# EEM_Connectors.net
KiCad netlist of a schematic drawn in Altium Designer
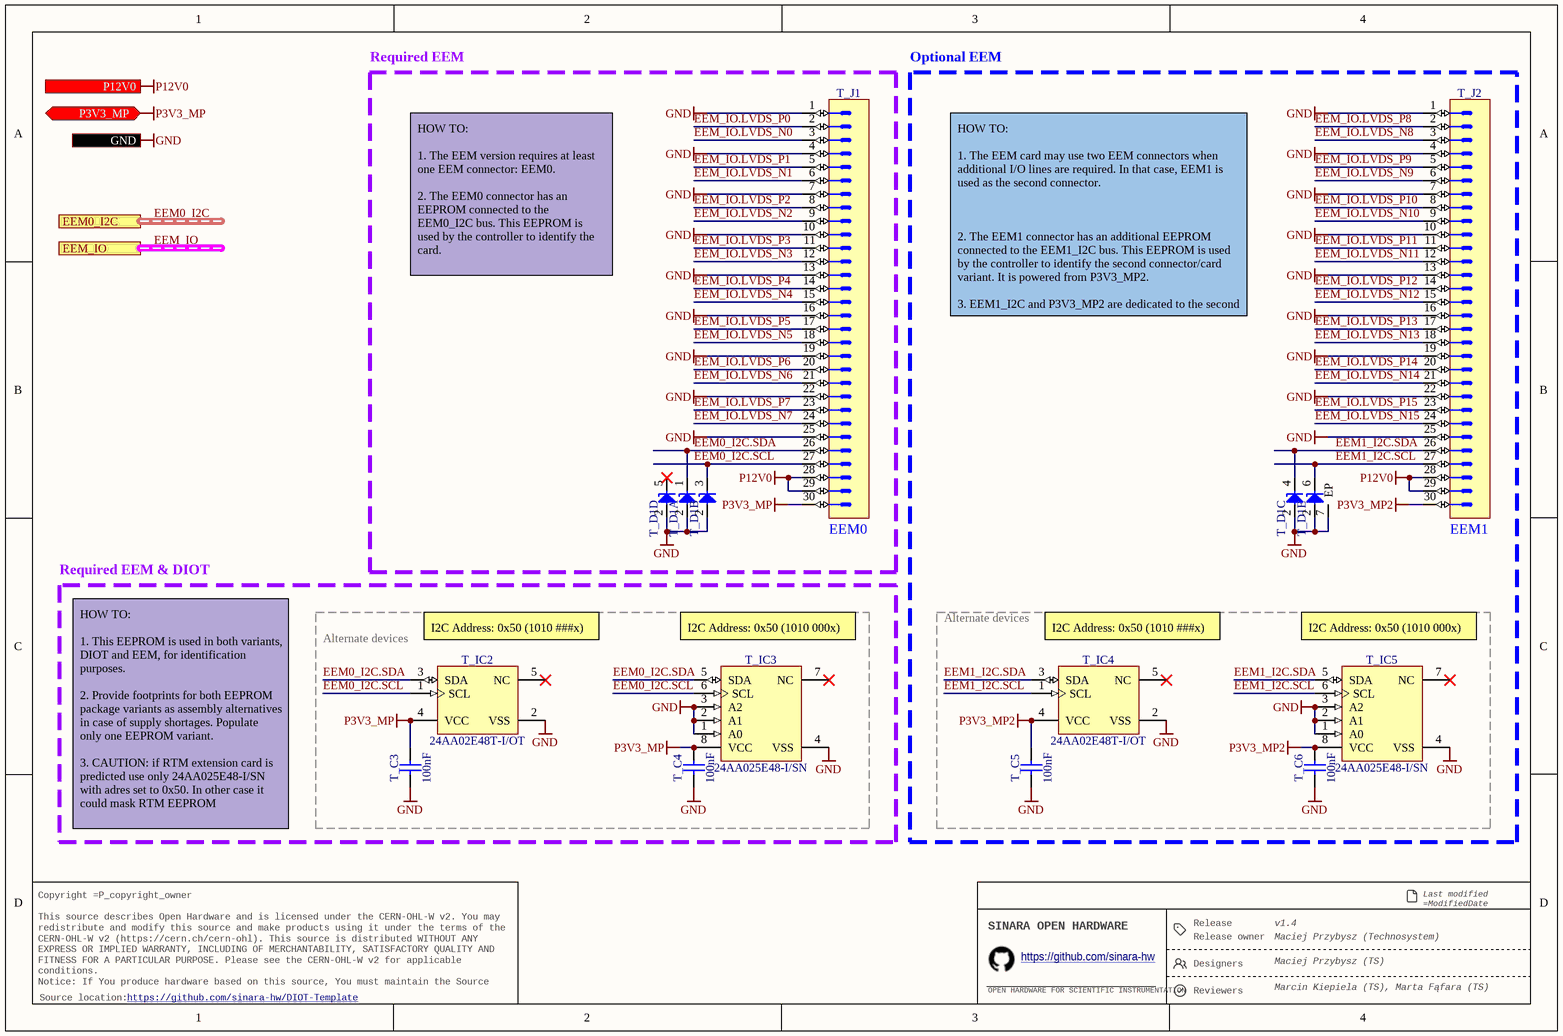
[diagram p0: EEM_Connectors.SchDoc]

(export (version "E")
  (design (tool "Eeschema 10.0.6"))
  (components
    (comp (ref "T_C3")
      (value "100nF")
      (footprint "CAPC1005X55N")
      (description "Non-polarised capacitor")
      (fields
        (field (name "PART NUMBER") "CC0402_100NF_50V_10%_X7R")
        (field (name "VOLTAGE") "50V")
        (field (name "AUTHOR") "CERN DEM MR")
      )
      (libsource (lib "Capacitors") (part "Capacitor - non polarized"))
    )
    (comp (ref "T_C4")
      (value "100nF")
      (footprint "CAPC1005X55N")
      (description "Non-polarised capacitor")
      (fields
        (field (name "PART NUMBER") "CC0402_100NF_50V_10%_X7R")
        (field (name "VOLTAGE") "50V")
        (field (name "AUTHOR") "CERN DEM MR")
      )
      (libsource (lib "Capacitors") (part "Capacitor - non polarized"))
    )
    (comp (ref "T_C5")
      (value "100nF")
      (footprint "CAPC1005X55N")
      (description "Non-polarised capacitor")
      (fields
        (field (name "PART NUMBER") "CC0402_100NF_50V_10%_X7R")
        (field (name "VOLTAGE") "50V")
        (field (name "AUTHOR") "CERN DEM MR")
      )
      (libsource (lib "Capacitors") (part "Capacitor - non polarized"))
    )
    (comp (ref "T_C6")
      (value "100nF")
      (footprint "CAPC1005X55N")
      (description "Non-polarised capacitor")
      (fields
        (field (name "PART NUMBER") "CC0402_100NF_50V_10%_X7R")
        (field (name "VOLTAGE") "50V")
        (field (name "AUTHOR") "CERN DEM MR")
      )
      (libsource (lib "Capacitors") (part "Capacitor - non polarized"))
    )
    (comp (ref "T_D1")
      (value "UCLAMP3305P.TCT")
      (footprint "SON50P160X65_HS-7N")
      (description "Diode TVS Quint Common Anode Uni-Dir 3.3V 40W 6-Pin SLP EP T/R")
      (libsource (lib "TechnoSystem Workspace") (part "D-AK-2"))
    )
    (comp (ref "T_IC2")
      (value "24AA02E48T-I/OT")
      (footprint "SOT95P280X145-5N")
      (description "1.7V-5.5V, 2K I2C Serial EEPROM With EUI-48 Node Identity")
      (fields (field (name "MANUFACTURER") "MICROCHIP TECHNOLOGY") (field (name "AUTHOR") "CERN DEM MR"))
      (libsource (lib "ICs And Semiconductors") (part "24AA02E48T-I/OT"))
    )
    (comp (ref "T_IC3")
      (value "24AA025E48-I/SN")
      (footprint "SOIC127P600X175-8N")
      (description "1.7V-5.5V, 2K I2C™ Serial EEPROMs with EUI-48™ Node Identity")
      (fields (field (name "MANUFACTURER") "MICROCHIP TECHNOLOGY") (field (name "AUTHOR") "CERN DEM MR"))
      (libsource (lib "ICs And Semiconductors") (part "24AA025E48-I/SN"))
    )
    (comp (ref "T_IC4")
      (value "24AA02E48T-I/OT")
      (footprint "SOT95P280X145-5N")
      (description "1.7V-5.5V, 2K I2C Serial EEPROM With EUI-48 Node Identity")
      (fields (field (name "MANUFACTURER") "MICROCHIP TECHNOLOGY") (field (name "AUTHOR") "CERN DEM MR"))
      (libsource (lib "ICs And Semiconductors") (part "24AA02E48T-I/OT"))
    )
    (comp (ref "T_IC5")
      (value "24AA025E48-I/SN")
      (footprint "SOIC127P600X175-8N")
      (description "1.7V-5.5V, 2K I2C™ Serial EEPROMs with EUI-48™ Node Identity")
      (fields (field (name "MANUFACTURER") "MICROCHIP TECHNOLOGY") (field (name "AUTHOR") "CERN DEM MR"))
      (libsource (lib "ICs And Semiconductors") (part "24AA025E48-I/SN"))
    )
    (comp (ref "T_J1")
      (value "~")
      (footprint "3M_N2530-6002RB")
      (description "Connector 30 Male")
      (fields
        (field (name "PART NUMBER") "3M_N2530-6002RB")
        (field (name "MANUFACTURER") "3M")
        (field (name "AUTHOR") "CERN DEM JLC")
      )
      (libsource (lib "Connectors") (part "Connector 30 Male"))
    )
    (comp (ref "T_J2")
      (value "~")
      (footprint "3M_N2530-6002RB")
      (description "Connector 30 Male")
      (fields
        (field (name "PART NUMBER") "3M_N2530-6002RB")
        (field (name "MANUFACTURER") "3M")
        (field (name "AUTHOR") "CERN DEM JLC")
      )
      (libsource (lib "Connectors") (part "Connector 30 Male"))
    )
  )
  (nets
    (net (code "3") (name "/EEM0_I2C.SCL") (class "Default")
      (node (ref "T_D1") (pin "3") (pinfunction "C_3") (pintype "passive"))
      (node (ref "T_IC2") (pin "1") (pinfunction "SCL_1") (pintype "input"))
      (node (ref "T_IC3") (pin "6") (pinfunction "SCL_6") (pintype "input"))
      (node (ref "T_J1") (pin "27") (pinfunction "27_27") (pintype "bidirectional"))
    )
    (net (code "4") (name "/EEM0_I2C.SDA") (class "Default")
      (node (ref "T_D1") (pin "1") (pinfunction "C_1") (pintype "passive"))
      (node (ref "T_IC2") (pin "3") (pinfunction "SDA_3") (pintype "bidirectional"))
      (node (ref "T_IC3") (pin "5") (pinfunction "SDA_5") (pintype "bidirectional"))
      (node (ref "T_J1") (pin "26") (pinfunction "26_26") (pintype "bidirectional"))
    )
    (net (code "5") (name "/EEM1_I2C.SCL") (class "Default")
      (node (ref "T_D1") (pin "6") (pinfunction "C_6") (pintype "passive"))
      (node (ref "T_IC4") (pin "1") (pinfunction "SCL_1") (pintype "input"))
      (node (ref "T_IC5") (pin "6") (pinfunction "SCL_6") (pintype "input"))
      (node (ref "T_J2") (pin "27") (pinfunction "27_27") (pintype "bidirectional"))
    )
    (net (code "6") (name "/EEM1_I2C.SDA") (class "Default")
      (node (ref "T_D1") (pin "4") (pinfunction "C_4") (pintype "passive"))
      (node (ref "T_IC4") (pin "3") (pinfunction "SDA_3") (pintype "bidirectional"))
      (node (ref "T_IC5") (pin "5") (pinfunction "SDA_5") (pintype "bidirectional"))
      (node (ref "T_J2") (pin "26") (pinfunction "26_26") (pintype "bidirectional"))
    )
    (net (code "7") (name "/EEM_IO.LVDS_N0") (class "Default")
      (node (ref "T_J1") (pin "3") (pinfunction "3_3") (pintype "bidirectional"))
    )
    (net (code "8") (name "/EEM_IO.LVDS_N1") (class "Default")
      (node (ref "T_J1") (pin "6") (pinfunction "6_6") (pintype "bidirectional"))
    )
    (net (code "9") (name "/EEM_IO.LVDS_N2") (class "Default")
      (node (ref "T_J1") (pin "9") (pinfunction "9_9") (pintype "bidirectional"))
    )
    (net (code "10") (name "/EEM_IO.LVDS_N3") (class "Default")
      (node (ref "T_J1") (pin "12") (pinfunction "12_12") (pintype "bidirectional"))
    )
    (net (code "11") (name "/EEM_IO.LVDS_N4") (class "Default")
      (node (ref "T_J1") (pin "15") (pinfunction "15_15") (pintype "bidirectional"))
    )
    (net (code "12") (name "/EEM_IO.LVDS_N5") (class "Default")
      (node (ref "T_J1") (pin "18") (pinfunction "18_18") (pintype "bidirectional"))
    )
    (net (code "13") (name "/EEM_IO.LVDS_N6") (class "Default")
      (node (ref "T_J1") (pin "21") (pinfunction "21_21") (pintype "bidirectional"))
    )
    (net (code "14") (name "/EEM_IO.LVDS_N7") (class "Default")
      (node (ref "T_J1") (pin "24") (pinfunction "24_24") (pintype "bidirectional"))
    )
    (net (code "15") (name "/EEM_IO.LVDS_N8") (class "Default")
      (node (ref "T_J2") (pin "3") (pinfunction "3_3") (pintype "bidirectional"))
    )
    (net (code "16") (name "/EEM_IO.LVDS_N9") (class "Default")
      (node (ref "T_J2") (pin "6") (pinfunction "6_6") (pintype "bidirectional"))
    )
    (net (code "17") (name "/EEM_IO.LVDS_N10") (class "Default")
      (node (ref "T_J2") (pin "9") (pinfunction "9_9") (pintype "bidirectional"))
    )
    (net (code "18") (name "/EEM_IO.LVDS_N11") (class "Default")
      (node (ref "T_J2") (pin "12") (pinfunction "12_12") (pintype "bidirectional"))
    )
    (net (code "19") (name "/EEM_IO.LVDS_N12") (class "Default")
      (node (ref "T_J2") (pin "15") (pinfunction "15_15") (pintype "bidirectional"))
    )
    (net (code "20") (name "/EEM_IO.LVDS_N13") (class "Default")
      (node (ref "T_J2") (pin "18") (pinfunction "18_18") (pintype "bidirectional"))
    )
    (net (code "21") (name "/EEM_IO.LVDS_N14") (class "Default")
      (node (ref "T_J2") (pin "21") (pinfunction "21_21") (pintype "bidirectional"))
    )
    (net (code "22") (name "/EEM_IO.LVDS_N15") (class "Default")
      (node (ref "T_J2") (pin "24") (pinfunction "24_24") (pintype "bidirectional"))
    )
    (net (code "23") (name "/EEM_IO.LVDS_P0") (class "Default")
      (node (ref "T_J1") (pin "2") (pinfunction "2_2") (pintype "bidirectional"))
    )
    (net (code "24") (name "/EEM_IO.LVDS_P1") (class "Default")
      (node (ref "T_J1") (pin "5") (pinfunction "5_5") (pintype "bidirectional"))
    )
    (net (code "25") (name "/EEM_IO.LVDS_P2") (class "Default")
      (node (ref "T_J1") (pin "8") (pinfunction "8_8") (pintype "bidirectional"))
    )
    (net (code "26") (name "/EEM_IO.LVDS_P3") (class "Default")
      (node (ref "T_J1") (pin "11") (pinfunction "11_11") (pintype "bidirectional"))
    )
    (net (code "27") (name "/EEM_IO.LVDS_P4") (class "Default")
      (node (ref "T_J1") (pin "14") (pinfunction "14_14") (pintype "bidirectional"))
    )
    (net (code "28") (name "/EEM_IO.LVDS_P5") (class "Default")
      (node (ref "T_J1") (pin "17") (pinfunction "17_17") (pintype "bidirectional"))
    )
    (net (code "29") (name "/EEM_IO.LVDS_P6") (class "Default")
      (node (ref "T_J1") (pin "20") (pinfunction "20_20") (pintype "bidirectional"))
    )
    (net (code "30") (name "/EEM_IO.LVDS_P7") (class "Default")
      (node (ref "T_J1") (pin "23") (pinfunction "23_23") (pintype "bidirectional"))
    )
    (net (code "31") (name "/EEM_IO.LVDS_P8") (class "Default")
      (node (ref "T_J2") (pin "2") (pinfunction "2_2") (pintype "bidirectional"))
    )
    (net (code "32") (name "/EEM_IO.LVDS_P9") (class "Default")
      (node (ref "T_J2") (pin "5") (pinfunction "5_5") (pintype "bidirectional"))
    )
    (net (code "33") (name "/EEM_IO.LVDS_P10") (class "Default")
      (node (ref "T_J2") (pin "8") (pinfunction "8_8") (pintype "bidirectional"))
    )
    (net (code "34") (name "/EEM_IO.LVDS_P11") (class "Default")
      (node (ref "T_J2") (pin "11") (pinfunction "11_11") (pintype "bidirectional"))
    )
    (net (code "35") (name "/EEM_IO.LVDS_P12") (class "Default")
      (node (ref "T_J2") (pin "14") (pinfunction "14_14") (pintype "bidirectional"))
    )
    (net (code "36") (name "/EEM_IO.LVDS_P13") (class "Default")
      (node (ref "T_J2") (pin "17") (pinfunction "17_17") (pintype "bidirectional"))
    )
    (net (code "37") (name "/EEM_IO.LVDS_P14") (class "Default")
      (node (ref "T_J2") (pin "20") (pinfunction "20_20") (pintype "bidirectional"))
    )
    (net (code "38") (name "/EEM_IO.LVDS_P15") (class "Default")
      (node (ref "T_J2") (pin "23") (pinfunction "23_23") (pintype "bidirectional"))
    )
    (net (code "41") (name "GND") (class "Default")
      (node (ref "T_C3") (pin "1") (pinfunction "1_1") (pintype "passive"))
      (node (ref "T_C4") (pin "1") (pinfunction "1_1") (pintype "passive"))
      (node (ref "T_C5") (pin "1") (pinfunction "1_1") (pintype "passive"))
      (node (ref "T_C6") (pin "1") (pinfunction "1_1") (pintype "passive"))
      (node (ref "T_D1") (pin "2") (pinfunction "A_2") (pintype "passive"))
      (node (ref "T_D1") (pin "7") (pinfunction "EP_7") (pintype "passive"))
      (node (ref "T_IC2") (pin "2") (pinfunction "VSS_2") (pintype "power_in"))
      (node (ref "T_IC3") (pin "1") (pinfunction "A0_1") (pintype "input"))
      (node (ref "T_IC3") (pin "2") (pinfunction "A1_2") (pintype "input"))
      (node (ref "T_IC3") (pin "3") (pinfunction "A2_3") (pintype "input"))
      (node (ref "T_IC3") (pin "4") (pinfunction "VSS_4") (pintype "power_in"))
      (node (ref "T_IC4") (pin "2") (pinfunction "VSS_2") (pintype "power_in"))
      (node (ref "T_IC5") (pin "1") (pinfunction "A0_1") (pintype "input"))
      (node (ref "T_IC5") (pin "2") (pinfunction "A1_2") (pintype "input"))
      (node (ref "T_IC5") (pin "3") (pinfunction "A2_3") (pintype "input"))
      (node (ref "T_IC5") (pin "4") (pinfunction "VSS_4") (pintype "power_in"))
      (node (ref "T_J1") (pin "1") (pinfunction "1_1") (pintype "bidirectional"))
      (node (ref "T_J1") (pin "10") (pinfunction "10_10") (pintype "bidirectional"))
      (node (ref "T_J1") (pin "13") (pinfunction "13_13") (pintype "bidirectional"))
      (node (ref "T_J1") (pin "16") (pinfunction "16_16") (pintype "bidirectional"))
      (node (ref "T_J1") (pin "19") (pinfunction "19_19") (pintype "bidirectional"))
      (node (ref "T_J1") (pin "22") (pinfunction "22_22") (pintype "bidirectional"))
      (node (ref "T_J1") (pin "25") (pinfunction "25_25") (pintype "bidirectional"))
      (node (ref "T_J1") (pin "4") (pinfunction "4_4") (pintype "bidirectional"))
      (node (ref "T_J1") (pin "7") (pinfunction "7_7") (pintype "bidirectional"))
      (node (ref "T_J2") (pin "1") (pinfunction "1_1") (pintype "bidirectional"))
      (node (ref "T_J2") (pin "10") (pinfunction "10_10") (pintype "bidirectional"))
      (node (ref "T_J2") (pin "13") (pinfunction "13_13") (pintype "bidirectional"))
      (node (ref "T_J2") (pin "16") (pinfunction "16_16") (pintype "bidirectional"))
      (node (ref "T_J2") (pin "19") (pinfunction "19_19") (pintype "bidirectional"))
      (node (ref "T_J2") (pin "22") (pinfunction "22_22") (pintype "bidirectional"))
      (node (ref "T_J2") (pin "25") (pinfunction "25_25") (pintype "bidirectional"))
      (node (ref "T_J2") (pin "4") (pinfunction "4_4") (pintype "bidirectional"))
      (node (ref "T_J2") (pin "7") (pinfunction "7_7") (pintype "bidirectional"))
    )
    (net (code "42") (name "P3V3_MP") (class "Default")
      (node (ref "T_C3") (pin "2") (pinfunction "2_2") (pintype "passive"))
      (node (ref "T_C4") (pin "2") (pinfunction "2_2") (pintype "passive"))
      (node (ref "T_IC2") (pin "4") (pinfunction "VCC_4") (pintype "power_in"))
      (node (ref "T_IC3") (pin "8") (pinfunction "VCC_8") (pintype "power_in"))
      (node (ref "T_J1") (pin "30") (pinfunction "30_30") (pintype "bidirectional"))
    )
    (net (code "43") (name "P3V3_MP2") (class "Default")
      (node (ref "T_C5") (pin "2") (pinfunction "2_2") (pintype "passive"))
      (node (ref "T_C6") (pin "2") (pinfunction "2_2") (pintype "passive"))
      (node (ref "T_IC4") (pin "4") (pinfunction "VCC_4") (pintype "power_in"))
      (node (ref "T_IC5") (pin "8") (pinfunction "VCC_8") (pintype "power_in"))
      (node (ref "T_J2") (pin "30") (pinfunction "30_30") (pintype "bidirectional"))
    )
    (net (code "44") (name "P12V0") (class "Default")
      (node (ref "T_J1") (pin "28") (pinfunction "28_28") (pintype "bidirectional"))
      (node (ref "T_J1") (pin "29") (pinfunction "29_29") (pintype "bidirectional"))
      (node (ref "T_J2") (pin "28") (pinfunction "28_28") (pintype "bidirectional"))
      (node (ref "T_J2") (pin "29") (pinfunction "29_29") (pintype "bidirectional"))
    )
    (net (code "45") (name "unconnected-(T_D1D-C-Pad5)") (class "Default")
      (node (ref "T_D1") (pin "5") (pinfunction "C_5") (pintype "passive+no_connect"))
    )
    (net (code "46") (name "unconnected-(T_IC2-NC-Pad5)") (class "Default")
      (node (ref "T_IC2") (pin "5") (pinfunction "NC_5") (pintype "passive+no_connect"))
    )
    (net (code "47") (name "unconnected-(T_IC3-NC-Pad7)") (class "Default")
      (node (ref "T_IC3") (pin "7") (pinfunction "NC_7") (pintype "passive+no_connect"))
    )
    (net (code "48") (name "unconnected-(T_IC4-NC-Pad5)") (class "Default")
      (node (ref "T_IC4") (pin "5") (pinfunction "NC_5") (pintype "passive+no_connect"))
    )
    (net (code "49") (name "unconnected-(T_IC5-NC-Pad7)") (class "Default")
      (node (ref "T_IC5") (pin "7") (pinfunction "NC_7") (pintype "passive+no_connect"))
    )
  )
)
